# Power_Supply.net
KiCad netlist of a schematic drawn in Altium Designer
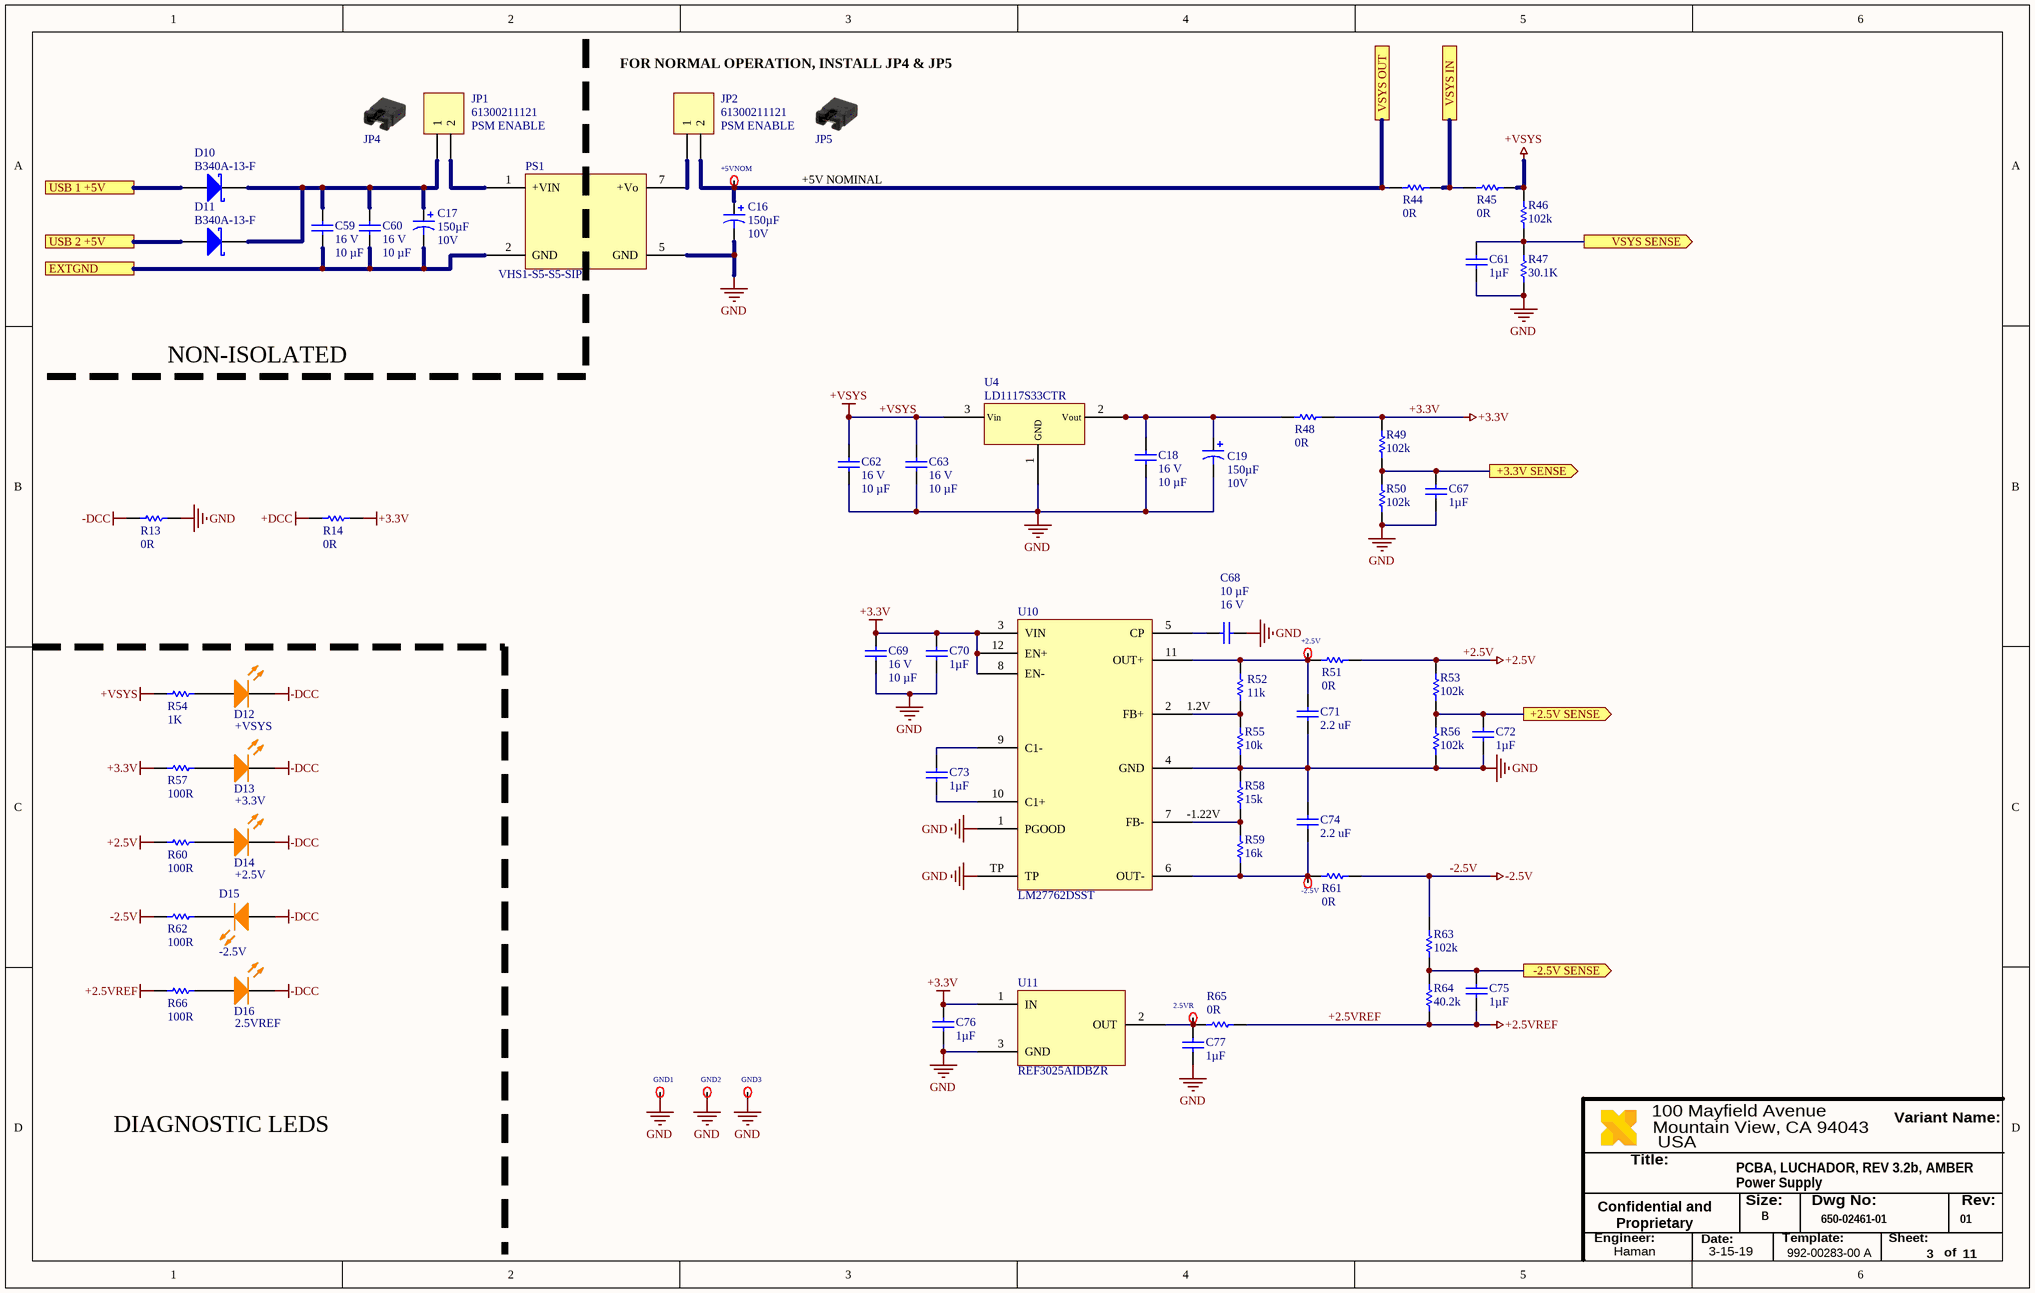
[diagram p0: Power Supply.SchDoc]

(export (version "E")
  (design (tool "Eeschema 10.0.6"))
  (components
    (comp (ref "+2.5V")
      (value "5001")
      (footprint "KEYSTONE TP")
      (fields (field (name "MANUFACTURER") "Keystone Electronics"))
      (libsource (lib "UTF SCHLIB") (part "5001"))
    )
    (comp (ref "+5VNOM")
      (value "5001")
      (footprint "KEYSTONE TP")
      (fields (field (name "MANUFACTURER") "Keystone Electronics"))
      (libsource (lib "UTF SCHLIB") (part "5001"))
    )
    (comp (ref "-2.5V")
      (value "5001")
      (footprint "KEYSTONE TP")
      (fields (field (name "MANUFACTURER") "Keystone Electronics"))
      (libsource (lib "UTF SCHLIB") (part "5001"))
    )
    (comp (ref "2.5VR")
      (value "5001")
      (footprint "KEYSTONE TP")
      (fields (field (name "MANUFACTURER") "Keystone Electronics"))
      (libsource (lib "UTF SCHLIB") (part "5001"))
    )
    (comp (ref "C16")
      (value "Cap Pol1")
      (footprint "2917")
      (description "Polarized Capacitor (Radial)")
      (fields
        (field (name "MANUFACTURER") "KEMET")
        (field (name "MANUFACTURER PART NUMBER") "T530D157M010ATE005")
        (field (name "CAPACITANCE") "150µF")
        (field (name "VOLTAGE - RATED") "10V")
      )
      (libsource (lib "Miscellaneous Devices") (part "Cap Pol1"))
    )
    (comp (ref "C17")
      (value "Cap Pol1")
      (footprint "2917")
      (description "Polarized Capacitor (Radial)")
      (fields
        (field (name "MANUFACTURER") "KEMET")
        (field (name "MANUFACTURER PART NUMBER") "T530D157M010ATE005")
        (field (name "CAPACITANCE") "150µF")
        (field (name "VOLTAGE - RATED") "10V")
      )
      (libsource (lib "Miscellaneous Devices") (part "Cap Pol1"))
    )
    (comp (ref "C18")
      (value "50V")
      (footprint "1206C")
      (description "CAP .1UF 50V CERAMIC Y5V 0805")
      (fields
        (field (name "MANUFACTURER") "Murata")
        (field (name "MANUFACTURER PART NUMBER") "GRM31CR71C106KA12L")
        (field (name "NOMINAL VOLTAGE") "16 V")
        (field (name "CAPACITY (ELEC.)") "10 µF")
      )
      (libsource (lib "Miscellaneous Devices") (part "Cap"))
    )
    (comp (ref "C19")
      (value "Cap Pol1")
      (footprint "2917")
      (description "Polarized Capacitor (Radial)")
      (fields
        (field (name "MANUFACTURER") "KEMET")
        (field (name "MANUFACTURER PART NUMBER") "T530D157M010ATE005")
        (field (name "CAPACITANCE") "150µF")
        (field (name "VOLTAGE - RATED") "10V")
      )
      (libsource (lib "Miscellaneous Devices") (part "Cap Pol1"))
    )
    (comp (ref "C59")
      (value "50V")
      (footprint "1206C")
      (description "CAP .1UF 50V CERAMIC Y5V 0805")
      (fields
        (field (name "MANUFACTURER") "Murata")
        (field (name "MANUFACTURER PART NUMBER") "GRM31CR71C106KA12L")
        (field (name "NOMINAL VOLTAGE") "16 V")
        (field (name "CAPACITY (ELEC.)") "10 µF")
      )
      (libsource (lib "Miscellaneous Devices") (part "Cap"))
    )
    (comp (ref "C60")
      (value "50V")
      (footprint "1206C")
      (description "CAP .1UF 50V CERAMIC Y5V 0805")
      (fields
        (field (name "MANUFACTURER") "Murata")
        (field (name "MANUFACTURER PART NUMBER") "GRM31CR71C106KA12L")
        (field (name "NOMINAL VOLTAGE") "16 V")
        (field (name "CAPACITY (ELEC.)") "10 µF")
      )
      (libsource (lib "Miscellaneous Devices") (part "Cap"))
    )
    (comp (ref "C61")
      (value "50V")
      (footprint "0402C")
      (description "CAP .1UF 50V CERAMIC Y5V 0805")
      (fields
        (field (name "MANUFACTURER") "TDK")
        (field (name "MANUFACTURER PART NUMBER") "CGB2A1JB1C105K033BC")
        (field (name "CAPACITANCE") "1µF")
      )
      (libsource (lib "Miscellaneous Devices") (part "Cap"))
    )
    (comp (ref "C62")
      (value "50V")
      (footprint "1206C")
      (description "CAP .1UF 50V CERAMIC Y5V 0805")
      (fields
        (field (name "MANUFACTURER") "Murata")
        (field (name "MANUFACTURER PART NUMBER") "GRM31CR71C106KA12L")
        (field (name "NOMINAL VOLTAGE") "16 V")
        (field (name "CAPACITY (ELEC.)") "10 µF")
      )
      (libsource (lib "Miscellaneous Devices") (part "Cap"))
    )
    (comp (ref "C63")
      (value "50V")
      (footprint "1206C")
      (description "CAP .1UF 50V CERAMIC Y5V 0805")
      (fields
        (field (name "MANUFACTURER") "Murata")
        (field (name "MANUFACTURER PART NUMBER") "GRM31CR71C106KA12L")
        (field (name "NOMINAL VOLTAGE") "16 V")
        (field (name "CAPACITY (ELEC.)") "10 µF")
      )
      (libsource (lib "Miscellaneous Devices") (part "Cap"))
    )
    (comp (ref "C67")
      (value "50V")
      (footprint "0402C")
      (description "CAP .1UF 50V CERAMIC Y5V 0805")
      (fields
        (field (name "MANUFACTURER") "TDK")
        (field (name "MANUFACTURER PART NUMBER") "CGB2A1JB1C105K033BC")
        (field (name "CAPACITANCE") "1µF")
      )
      (libsource (lib "Miscellaneous Devices") (part "Cap"))
    )
    (comp (ref "C68")
      (value "50V")
      (footprint "1206C")
      (description "CAP .1UF 50V CERAMIC Y5V 0805")
      (fields
        (field (name "MANUFACTURER") "Murata")
        (field (name "MANUFACTURER PART NUMBER") "GRM31CR71C106KA12L")
        (field (name "NOMINAL VOLTAGE") "16 V")
        (field (name "CAPACITY (ELEC.)") "10 µF")
      )
      (libsource (lib "Miscellaneous Devices") (part "Cap"))
    )
    (comp (ref "C69")
      (value "50V")
      (footprint "1206C")
      (description "CAP .1UF 50V CERAMIC Y5V 0805")
      (fields
        (field (name "MANUFACTURER") "Murata")
        (field (name "MANUFACTURER PART NUMBER") "GRM31CR71C106KA12L")
        (field (name "NOMINAL VOLTAGE") "16 V")
        (field (name "CAPACITY (ELEC.)") "10 µF")
      )
      (libsource (lib "Miscellaneous Devices") (part "Cap"))
    )
    (comp (ref "C70")
      (value "50V")
      (footprint "0402C")
      (description "CAP .1UF 50V CERAMIC Y5V 0805")
      (fields
        (field (name "MANUFACTURER") "TDK")
        (field (name "MANUFACTURER PART NUMBER") "CGB2A1JB1C105K033BC")
        (field (name "CAPACITANCE") "1µF")
      )
      (libsource (lib "Miscellaneous Devices") (part "Cap"))
    )
    (comp (ref "C71")
      (value "50V")
      (footprint "0402C")
      (description "CAP .1UF 50V CERAMIC Y5V 0805")
      (fields
        (field (name "MANUFACTURER") "Samsung")
        (field (name "MANUFACTURER PART NUMBER") "CL05A225KO5NQNC")
        (field (name "CAPACITANCE VALUE") "2.2 uF")
      )
      (libsource (lib "Miscellaneous Devices") (part "Cap"))
    )
    (comp (ref "C72")
      (value "50V")
      (footprint "0402C")
      (description "CAP .1UF 50V CERAMIC Y5V 0805")
      (fields
        (field (name "MANUFACTURER") "TDK")
        (field (name "MANUFACTURER PART NUMBER") "CGB2A1JB1C105K033BC")
        (field (name "CAPACITANCE") "1µF")
      )
      (libsource (lib "Miscellaneous Devices") (part "Cap"))
    )
    (comp (ref "C73")
      (value "50V")
      (footprint "0402C")
      (description "CAP .1UF 50V CERAMIC Y5V 0805")
      (fields
        (field (name "MANUFACTURER") "TDK")
        (field (name "MANUFACTURER PART NUMBER") "CGB2A1JB1C105K033BC")
        (field (name "CAPACITANCE") "1µF")
      )
      (libsource (lib "Miscellaneous Devices") (part "Cap"))
    )
    (comp (ref "C74")
      (value "50V")
      (footprint "0402C")
      (description "CAP .1UF 50V CERAMIC Y5V 0805")
      (fields
        (field (name "MANUFACTURER") "Samsung")
        (field (name "MANUFACTURER PART NUMBER") "CL05A225KO5NQNC")
        (field (name "CAPACITANCE VALUE") "2.2 uF")
      )
      (libsource (lib "Miscellaneous Devices") (part "Cap"))
    )
    (comp (ref "C75")
      (value "50V")
      (footprint "0402C")
      (description "CAP .1UF 50V CERAMIC Y5V 0805")
      (fields
        (field (name "MANUFACTURER") "TDK")
        (field (name "MANUFACTURER PART NUMBER") "CGB2A1JB1C105K033BC")
        (field (name "CAPACITANCE") "1µF")
      )
      (libsource (lib "Miscellaneous Devices") (part "Cap"))
    )
    (comp (ref "C76")
      (value "50V")
      (footprint "0402C")
      (description "CAP .1UF 50V CERAMIC Y5V 0805")
      (fields
        (field (name "MANUFACTURER") "TDK")
        (field (name "MANUFACTURER PART NUMBER") "CGB2A1JB1C105K033BC")
        (field (name "CAPACITANCE") "1µF")
      )
      (libsource (lib "Miscellaneous Devices") (part "Cap"))
    )
    (comp (ref "C77")
      (value "50V")
      (footprint "0402C")
      (description "CAP .1UF 50V CERAMIC Y5V 0805")
      (fields
        (field (name "MANUFACTURER") "TDK")
        (field (name "MANUFACTURER PART NUMBER") "CGB2A1JB1C105K033BC")
        (field (name "CAPACITANCE") "1µF")
      )
      (libsource (lib "Miscellaneous Devices") (part "Cap"))
    )
    (comp (ref "D10")
      (value "BAT46ZFILM")
      (footprint "SMA")
      (description "Schottky Rectifier")
      (fields
        (field (name "MANUFACTURER") "Diodes Incorporated")
        (field (name "MANUFACTURER PART NUMBER") "B340A-13-F")
      )
      (libsource (lib "EEG_SCHLIB") (part "BAT46ZFILM"))
    )
    (comp (ref "D11")
      (value "BAT46ZFILM")
      (footprint "SMA")
      (description "Schottky Rectifier")
      (fields
        (field (name "MANUFACTURER") "Diodes Incorporated")
        (field (name "MANUFACTURER PART NUMBER") "B340A-13-F")
      )
      (libsource (lib "EEG_SCHLIB") (part "BAT46ZFILM"))
    )
    (comp (ref "D12")
      (value "+VSYS")
      (footprint "0402L-ORANGE")
      (description "Typical INFRARED GaAs LED")
      (fields
        (field (name "MANUFACTURER") "Vishay")
        (field (name "MANUFACTURER PART NUMBER") "VLMO1500-GS08")
      )
      (libsource (lib "LUCHADOR SCHLIB") (part "LED0_1"))
    )
    (comp (ref "D13")
      (value "+3.3V")
      (footprint "0402L-ORANGE")
      (description "Typical INFRARED GaAs LED")
      (fields
        (field (name "MANUFACTURER") "Vishay")
        (field (name "MANUFACTURER PART NUMBER") "VLMO1500-GS08")
      )
      (libsource (lib "LUCHADOR SCHLIB") (part "LED0_1"))
    )
    (comp (ref "D14")
      (value "+2.5V")
      (footprint "0402L-ORANGE")
      (description "Typical INFRARED GaAs LED")
      (fields
        (field (name "MANUFACTURER") "Vishay")
        (field (name "MANUFACTURER PART NUMBER") "VLMO1500-GS08")
      )
      (libsource (lib "LUCHADOR SCHLIB") (part "LED0_1"))
    )
    (comp (ref "D15")
      (value "-2.5V")
      (footprint "0402L-ORANGE")
      (description "Typical INFRARED GaAs LED")
      (fields
        (field (name "MANUFACTURER") "Vishay")
        (field (name "MANUFACTURER PART NUMBER") "VLMO1500-GS08")
      )
      (libsource (lib "LUCHADOR SCHLIB") (part "LED0_1"))
    )
    (comp (ref "D16")
      (value "2.5VREF")
      (footprint "0402L-ORANGE")
      (description "Typical INFRARED GaAs LED")
      (fields
        (field (name "MANUFACTURER") "Vishay")
        (field (name "MANUFACTURER PART NUMBER") "VLMO1500-GS08")
      )
      (libsource (lib "LUCHADOR SCHLIB") (part "LED0_1"))
    )
    (comp (ref "GND1")
      (value "5001")
      (footprint "KEYSTONE TP")
      (fields (field (name "MANUFACTURER") "Keystone Electronics"))
      (libsource (lib "UTF SCHLIB") (part "5001"))
    )
    (comp (ref "GND2")
      (value "5001")
      (footprint "KEYSTONE TP")
      (fields (field (name "MANUFACTURER") "Keystone Electronics"))
      (libsource (lib "UTF SCHLIB") (part "5001"))
    )
    (comp (ref "GND3")
      (value "5001")
      (footprint "KEYSTONE TP")
      (fields (field (name "MANUFACTURER") "Keystone Electronics"))
      (libsource (lib "UTF SCHLIB") (part "5001"))
    )
    (comp (ref "JP1")
      (value "PSM ENABLE")
      (footprint "61300211121")
      (description "Header, 2-Pin")
      (fields
        (field (name "MANUFACTURER") "Wurth Electronics")
        (field (name "MANUFACTURER PART NUMBER") "61300211121")
      )
      (libsource (lib "Miscellaneous Connectors") (part "Header 2"))
    )
    (comp (ref "JP2")
      (value "PSM ENABLE")
      (footprint "61300211121")
      (description "Header, 2-Pin")
      (fields
        (field (name "MANUFACTURER") "Wurth Electronics")
        (field (name "MANUFACTURER PART NUMBER") "61300211121")
      )
      (libsource (lib "Miscellaneous Connectors") (part "Header 2"))
    )
    (comp (ref "JP4")
      (value "QPC02SXGN-RC")
      (fields (field (name "MANUFACTURER") "Sullins"))
      (libsource (lib "LUCHADOR SCHLIB") (part "QPC02SXGN-RC"))
    )
    (comp (ref "JP5")
      (value "QPC02SXGN-RC")
      (fields (field (name "MANUFACTURER") "Sullins"))
      (libsource (lib "LUCHADOR SCHLIB") (part "QPC02SXGN-RC"))
    )
    (comp (ref "PS1")
      (value "VHS1-S5-S5-SIP")
      (footprint "ISOLATED MODULE")
      (fields (field (name "MANUFACTURER") "CUI") (field (name "MANUFACTURER PART NUMBER") "VHS1-S5-S5-SIP"))
      (libsource (lib "LUCHADOR SCHLIB") (part "VHS1-S5-S5-SIP"))
    )
    (comp (ref "R13")
      (value "Res 0805")
      (footprint "0402R")
      (description "Resistor")
      (fields
        (field (name "MANUFACTURER") "Panasonic")
        (field (name "MANUFACTURER PART NUMBER") "ERJ-2GE0R00X")
        (field (name "RESISTANCE (OHMS)") "0R")
      )
      (libsource (lib "RAPTOR MCB SCHLIB") (part "Res 0805"))
    )
    (comp (ref "R14")
      (value "Res 0805")
      (footprint "0402R")
      (description "Resistor")
      (fields
        (field (name "MANUFACTURER") "Panasonic")
        (field (name "MANUFACTURER PART NUMBER") "ERJ-2GE0R00X")
        (field (name "RESISTANCE (OHMS)") "0R")
      )
      (libsource (lib "RAPTOR MCB SCHLIB") (part "Res 0805"))
    )
    (comp (ref "R44")
      (value "Res 0805")
      (footprint "0402R")
      (description "Resistor")
      (fields
        (field (name "MANUFACTURER") "Panasonic")
        (field (name "MANUFACTURER PART NUMBER") "ERJ-2GE0R00X")
        (field (name "RESISTANCE (OHMS)") "0R")
      )
      (libsource (lib "RAPTOR MCB SCHLIB") (part "Res 0805"))
    )
    (comp (ref "R45")
      (value "Res 0805")
      (footprint "0402R")
      (description "Resistor")
      (fields
        (field (name "MANUFACTURER") "Panasonic")
        (field (name "MANUFACTURER PART NUMBER") "ERJ-2GE0R00X")
        (field (name "RESISTANCE (OHMS)") "0R")
      )
      (libsource (lib "RAPTOR MCB SCHLIB") (part "Res 0805"))
    )
    (comp (ref "R46")
      (value "Res 0805")
      (footprint "0402R")
      (description "Resistor")
      (fields
        (field (name "MANUFACTURER") "Panasonic")
        (field (name "MANUFACTURER PART NUMBER") "ERJ-2RKF1023X")
        (field (name "RESISTANCE") "102k")
      )
      (libsource (lib "RAPTOR MCB SCHLIB") (part "Res 0805"))
    )
    (comp (ref "R47")
      (value "Res 0805")
      (footprint "0402R")
      (description "Resistor")
      (fields
        (field (name "MANUFACTURER") "Panasonic")
        (field (name "MANUFACTURER PART NUMBER") "ERJ-2RKF3012X")
        (field (name "RESISTANCE") "30.1K")
      )
      (libsource (lib "RAPTOR MCB SCHLIB") (part "Res 0805"))
    )
    (comp (ref "R48")
      (value "Res 0805")
      (footprint "0402R")
      (description "Resistor")
      (fields
        (field (name "MANUFACTURER") "Panasonic")
        (field (name "MANUFACTURER PART NUMBER") "ERJ-2GE0R00X")
        (field (name "RESISTANCE (OHMS)") "0R")
      )
      (libsource (lib "RAPTOR MCB SCHLIB") (part "Res 0805"))
    )
    (comp (ref "R49")
      (value "Res 0805")
      (footprint "0402R")
      (description "Resistor")
      (fields
        (field (name "MANUFACTURER") "Panasonic")
        (field (name "MANUFACTURER PART NUMBER") "ERJ-2RKF1023X")
        (field (name "RESISTANCE") "102k")
      )
      (libsource (lib "RAPTOR MCB SCHLIB") (part "Res 0805"))
    )
    (comp (ref "R50")
      (value "Res 0805")
      (footprint "0402R")
      (description "Resistor")
      (fields
        (field (name "MANUFACTURER") "Panasonic")
        (field (name "MANUFACTURER PART NUMBER") "ERJ-2RKF1023X")
        (field (name "RESISTANCE") "102k")
      )
      (libsource (lib "RAPTOR MCB SCHLIB") (part "Res 0805"))
    )
    (comp (ref "R51")
      (value "Res 0805")
      (footprint "0402R")
      (description "Resistor")
      (fields
        (field (name "MANUFACTURER") "Panasonic")
        (field (name "MANUFACTURER PART NUMBER") "ERJ-2GE0R00X")
        (field (name "RESISTANCE (OHMS)") "0R")
      )
      (libsource (lib "RAPTOR MCB SCHLIB") (part "Res 0805"))
    )
    (comp (ref "R52")
      (value "Res 0805")
      (footprint "0402R")
      (description "Resistor")
      (fields
        (field (name "MANUFACTURER") "Yageo")
        (field (name "MANUFACTURER PART NUMBER") "RC0402FR-0711KL")
        (field (name "RESISTANCE") "11k")
      )
      (libsource (lib "RAPTOR MCB SCHLIB") (part "Res 0805"))
    )
    (comp (ref "R53")
      (value "Res 0805")
      (footprint "0402R")
      (description "Resistor")
      (fields
        (field (name "MANUFACTURER") "Panasonic")
        (field (name "MANUFACTURER PART NUMBER") "ERJ-2RKF1023X")
        (field (name "RESISTANCE") "102k")
      )
      (libsource (lib "RAPTOR MCB SCHLIB") (part "Res 0805"))
    )
    (comp (ref "R54")
      (value "Res 0805")
      (footprint "0402R")
      (description "Resistor")
      (fields
        (field (name "MANUFACTURER") "Yageo")
        (field (name "MANUFACTURER PART NUMBER") "RC0402FR-071KL")
        (field (name "RESISTANCE") "1K")
      )
      (libsource (lib "RAPTOR MCB SCHLIB") (part "Res 0805"))
    )
    (comp (ref "R55")
      (value "Res 0805")
      (footprint "0402R")
      (description "Resistor")
      (fields
        (field (name "MANUFACTURER") "Samsung")
        (field (name "MANUFACTURER PART NUMBER") "RC1005F103CS")
        (field (name "RESISTANCE") "10k")
      )
      (libsource (lib "RAPTOR MCB SCHLIB") (part "Res 0805"))
    )
    (comp (ref "R56")
      (value "Res 0805")
      (footprint "0402R")
      (description "Resistor")
      (fields
        (field (name "MANUFACTURER") "Panasonic")
        (field (name "MANUFACTURER PART NUMBER") "ERJ-2RKF1023X")
        (field (name "RESISTANCE") "102k")
      )
      (libsource (lib "RAPTOR MCB SCHLIB") (part "Res 0805"))
    )
    (comp (ref "R57")
      (value "Res 0805")
      (footprint "0402R")
      (description "Resistor")
      (fields
        (field (name "MANUFACTURER") "Panasonic")
        (field (name "MANUFACTURER PART NUMBER") "ERJ-2RKF1000X")
        (field (name "RESISTANCE") "100R")
      )
      (libsource (lib "RAPTOR MCB SCHLIB") (part "Res 0805"))
    )
    (comp (ref "R58")
      (value "Res 0805")
      (footprint "0402R")
      (description "Resistor")
      (fields
        (field (name "MANUFACTURER") "Panasonic")
        (field (name "MANUFACTURER PART NUMBER") "ERJ-2RKF1502X")
        (field (name "RESISTANCE") "15k")
      )
      (libsource (lib "RAPTOR MCB SCHLIB") (part "Res 0805"))
    )
    (comp (ref "R59")
      (value "Res 0805")
      (footprint "0402R")
      (description "Resistor")
      (fields
        (field (name "MANUFACTURER") "Panasonic")
        (field (name "MANUFACTURER PART NUMBER") "ERJ-2RKF1602X")
        (field (name "RESISTANCE") "16k")
      )
      (libsource (lib "RAPTOR MCB SCHLIB") (part "Res 0805"))
    )
    (comp (ref "R60")
      (value "Res 0805")
      (footprint "0402R")
      (description "Resistor")
      (fields
        (field (name "MANUFACTURER") "Panasonic")
        (field (name "MANUFACTURER PART NUMBER") "ERJ-2RKF1000X")
        (field (name "RESISTANCE") "100R")
      )
      (libsource (lib "RAPTOR MCB SCHLIB") (part "Res 0805"))
    )
    (comp (ref "R61")
      (value "Res 0805")
      (footprint "0402R")
      (description "Resistor")
      (fields
        (field (name "MANUFACTURER") "Panasonic")
        (field (name "MANUFACTURER PART NUMBER") "ERJ-2GE0R00X")
        (field (name "RESISTANCE (OHMS)") "0R")
      )
      (libsource (lib "RAPTOR MCB SCHLIB") (part "Res 0805"))
    )
    (comp (ref "R62")
      (value "Res 0805")
      (footprint "0402R")
      (description "Resistor")
      (fields
        (field (name "MANUFACTURER") "Panasonic")
        (field (name "MANUFACTURER PART NUMBER") "ERJ-2RKF1000X")
        (field (name "RESISTANCE") "100R")
      )
      (libsource (lib "RAPTOR MCB SCHLIB") (part "Res 0805"))
    )
    (comp (ref "R63")
      (value "Res 0805")
      (footprint "0402R")
      (description "Resistor")
      (fields
        (field (name "MANUFACTURER") "Panasonic")
        (field (name "MANUFACTURER PART NUMBER") "ERJ-2RKF1023X")
        (field (name "RESISTANCE") "102k")
      )
      (libsource (lib "RAPTOR MCB SCHLIB") (part "Res 0805"))
    )
    (comp (ref "R64")
      (value "Res 0805")
      (footprint "0402R")
      (description "Resistor")
      (fields
        (field (name "MANUFACTURER") "Panasonic")
        (field (name "MANUFACTURER PART NUMBER") "ERJ-2RKF4022X")
        (field (name "RESISTANCE") "40.2k")
      )
      (libsource (lib "RAPTOR MCB SCHLIB") (part "Res 0805"))
    )
    (comp (ref "R65")
      (value "Res 0805")
      (footprint "0402R")
      (description "Resistor")
      (fields
        (field (name "MANUFACTURER") "Panasonic")
        (field (name "MANUFACTURER PART NUMBER") "ERJ-2GE0R00X")
        (field (name "RESISTANCE (OHMS)") "0R")
      )
      (libsource (lib "RAPTOR MCB SCHLIB") (part "Res 0805"))
    )
    (comp (ref "R66")
      (value "Res 0805")
      (footprint "0402R")
      (description "Resistor")
      (fields
        (field (name "MANUFACTURER") "Panasonic")
        (field (name "MANUFACTURER PART NUMBER") "ERJ-2RKF1000X")
        (field (name "RESISTANCE") "100R")
      )
      (libsource (lib "RAPTOR MCB SCHLIB") (part "Res 0805"))
    )
    (comp (ref "U4")
      (value "LD1117S33CTR")
      (footprint "SOT-223")
      (fields
        (field (name "MANUFACTURER") "STMicroelectronics")
        (field (name "MANUFACTURER PART NUMBER") "LD1117S33CTR")
      )
      (libsource (lib "EEG_SCHLIB") (part "LD1117S33CTR"))
    )
    (comp (ref "U10")
      (value "LM27762DSST")
      (footprint "WFDFN-12")
      (fields
        (field (name "MANUFACTURER") "Texas Instruments")
        (field (name "MANUFACTURER PART NUMBER") "LM27762DSST")
      )
      (libsource (lib "LUCHADOR SCHLIB") (part "LM27762DSST"))
    )
    (comp (ref "U11")
      (value "REF3025AIDBZR")
      (footprint "SOT-23")
      (fields
        (field (name "MANUFACTURER") "Texas Instruments")
        (field (name "TOLERANCE") "±0.2%")
        (field (name "MANUFACTURER PART NUMBER") "REF3025AIDBZR")
      )
      (libsource (lib "LUCHADOR SCHLIB") (part "REF3025AIDBZR"))
    )
  )
  (nets
    (net (code "1") (name "+2.5V") (class "Default")
      (node (ref "R51") (pin "2") (pinfunction "2_2") (pintype "passive"))
      (node (ref "R53") (pin "2") (pinfunction "2_2") (pintype "passive"))
      (node (ref "R60") (pin "1") (pinfunction "1_1") (pintype "passive"))
    )
    (net (code "2") (name "+2.5VREF") (class "Default")
      (node (ref "C75") (pin "2") (pinfunction "2_2") (pintype "passive"))
      (node (ref "R64") (pin "1") (pinfunction "1_1") (pintype "passive"))
      (node (ref "R65") (pin "2") (pinfunction "2_2") (pintype "passive"))
      (node (ref "R66") (pin "1") (pinfunction "1_1") (pintype "passive"))
    )
    (net (code "3") (name "+3.3V") (class "Default")
      (node (ref "C69") (pin "1") (pinfunction "1_1") (pintype "passive"))
      (node (ref "C70") (pin "1") (pinfunction "1_1") (pintype "passive"))
      (node (ref "C76") (pin "1") (pinfunction "1_1") (pintype "passive"))
      (node (ref "R14") (pin "2") (pinfunction "2_2") (pintype "passive"))
      (node (ref "R48") (pin "2") (pinfunction "2_2") (pintype "passive"))
      (node (ref "R49") (pin "2") (pinfunction "2_2") (pintype "passive"))
      (node (ref "R57") (pin "1") (pinfunction "1_1") (pintype "passive"))
      (node (ref "U10") (pin "12") (pinfunction "EN+_12") (pintype "passive"))
      (node (ref "U10") (pin "3") (pinfunction "VIN_3") (pintype "passive"))
      (node (ref "U10") (pin "8") (pinfunction "EN-_8") (pintype "passive"))
      (node (ref "U11") (pin "1") (pinfunction "IN_1") (pintype "passive"))
    )
    (net (code "4") (name "+DCC") (class "Default")
      (node (ref "R14") (pin "1") (pinfunction "1_1") (pintype "passive"))
    )
    (net (code "5") (name "+VSYS") (class "Default")
      (node (ref "C62") (pin "1") (pinfunction "1_1") (pintype "passive"))
      (node (ref "C63") (pin "1") (pinfunction "1_1") (pintype "passive"))
      (node (ref "R45") (pin "2") (pinfunction "2_2") (pintype "passive"))
      (node (ref "R46") (pin "2") (pinfunction "2_2") (pintype "passive"))
      (node (ref "R54") (pin "1") (pinfunction "1_1") (pintype "passive"))
      (node (ref "U4") (pin "3") (pinfunction "Vin_3") (pintype "power_in"))
    )
    (net (code "6") (name "-2.5V") (class "Default")
      (node (ref "R61") (pin "2") (pinfunction "2_2") (pintype "passive"))
      (node (ref "R62") (pin "1") (pinfunction "1_1") (pintype "passive"))
      (node (ref "R63") (pin "2") (pinfunction "2_2") (pintype "passive"))
    )
    (net (code "7") (name "-DCC") (class "Default")
      (node (ref "D12") (pin "2") (pinfunction "K_2") (pintype "passive"))
      (node (ref "D13") (pin "2") (pinfunction "K_2") (pintype "passive"))
      (node (ref "D14") (pin "2") (pinfunction "K_2") (pintype "passive"))
      (node (ref "D15") (pin "1") (pinfunction "A_1") (pintype "passive"))
      (node (ref "D16") (pin "2") (pinfunction "K_2") (pintype "passive"))
      (node (ref "R13") (pin "1") (pinfunction "1_1") (pintype "passive"))
    )
    (net (code "8") (name "/+2.5V SENSE") (class "Default")
      (node (ref "C72") (pin "1") (pinfunction "1_1") (pintype "passive"))
      (node (ref "R53") (pin "1") (pinfunction "1_1") (pintype "passive"))
      (node (ref "R56") (pin "2") (pinfunction "2_2") (pintype "passive"))
    )
    (net (code "9") (name "/+3.3V SENSE") (class "Default")
      (node (ref "C67") (pin "1") (pinfunction "1_1") (pintype "passive"))
      (node (ref "R49") (pin "1") (pinfunction "1_1") (pintype "passive"))
      (node (ref "R50") (pin "2") (pinfunction "2_2") (pintype "passive"))
    )
    (net (code "10") (name "/-2.5V SENSE") (class "Default")
      (node (ref "C75") (pin "1") (pinfunction "1_1") (pintype "passive"))
      (node (ref "R63") (pin "1") (pinfunction "1_1") (pintype "passive"))
      (node (ref "R64") (pin "2") (pinfunction "2_2") (pintype "passive"))
    )
    (net (code "11") (name "/EXTGND") (class "Default")
      (node (ref "C17") (pin "2") (pinfunction "2_2") (pintype "passive"))
      (node (ref "C59") (pin "2") (pinfunction "2_2") (pintype "passive"))
      (node (ref "C60") (pin "2") (pinfunction "2_2") (pintype "passive"))
      (node (ref "PS1") (pin "2") (pinfunction "GND_2") (pintype "passive"))
    )
    (net (code "12") (name "/USB 1 +5V") (class "Default")
      (node (ref "D10") (pin "1") (pinfunction "A_1") (pintype "passive"))
    )
    (net (code "13") (name "/USB 2 +5V") (class "Default")
      (node (ref "D11") (pin "1") (pinfunction "A_1") (pintype "passive"))
    )
    (net (code "14") (name "/VSYS IN") (class "Default")
      (node (ref "R44") (pin "2") (pinfunction "2_2") (pintype "passive"))
      (node (ref "R45") (pin "1") (pinfunction "1_1") (pintype "passive"))
    )
    (net (code "15") (name "/VSYS OUT") (class "Default")
      (node (ref "+5VNOM") (pin "1") (pinfunction "1_1") (pintype "passive"))
      (node (ref "C16") (pin "1") (pinfunction "1_1") (pintype "passive"))
      (node (ref "JP2") (pin "2") (pinfunction "2_2") (pintype "passive"))
      (node (ref "R44") (pin "1") (pinfunction "1_1") (pintype "passive"))
    )
    (net (code "16") (name "/VSYS SENSE") (class "Default")
      (node (ref "C61") (pin "1") (pinfunction "1_1") (pintype "passive"))
      (node (ref "R46") (pin "1") (pinfunction "1_1") (pintype "passive"))
      (node (ref "R47") (pin "2") (pinfunction "2_2") (pintype "passive"))
    )
    (net (code "17") (name "GND") (class "Default")
      (node (ref "C16") (pin "2") (pinfunction "2_2") (pintype "passive"))
      (node (ref "C18") (pin "2") (pinfunction "2_2") (pintype "passive"))
      (node (ref "C19") (pin "2") (pinfunction "2_2") (pintype "passive"))
      (node (ref "C61") (pin "2") (pinfunction "2_2") (pintype "passive"))
      (node (ref "C62") (pin "2") (pinfunction "2_2") (pintype "passive"))
      (node (ref "C63") (pin "2") (pinfunction "2_2") (pintype "passive"))
      (node (ref "C67") (pin "2") (pinfunction "2_2") (pintype "passive"))
      (node (ref "C68") (pin "2") (pinfunction "2_2") (pintype "passive"))
      (node (ref "C69") (pin "2") (pinfunction "2_2") (pintype "passive"))
      (node (ref "C70") (pin "2") (pinfunction "2_2") (pintype "passive"))
      (node (ref "C71") (pin "2") (pinfunction "2_2") (pintype "passive"))
      (node (ref "C72") (pin "2") (pinfunction "2_2") (pintype "passive"))
      (node (ref "C74") (pin "1") (pinfunction "1_1") (pintype "passive"))
      (node (ref "C76") (pin "2") (pinfunction "2_2") (pintype "passive"))
      (node (ref "C77") (pin "2") (pinfunction "2_2") (pintype "passive"))
      (node (ref "GND1") (pin "1") (pinfunction "1_1") (pintype "passive"))
      (node (ref "GND2") (pin "1") (pinfunction "1_1") (pintype "passive"))
      (node (ref "GND3") (pin "1") (pinfunction "1_1") (pintype "passive"))
      (node (ref "PS1") (pin "5") (pinfunction "GND_5") (pintype "passive"))
      (node (ref "R13") (pin "2") (pinfunction "2_2") (pintype "passive"))
      (node (ref "R47") (pin "1") (pinfunction "1_1") (pintype "passive"))
      (node (ref "R50") (pin "1") (pinfunction "1_1") (pintype "passive"))
      (node (ref "R55") (pin "1") (pinfunction "1_1") (pintype "passive"))
      (node (ref "R56") (pin "1") (pinfunction "1_1") (pintype "passive"))
      (node (ref "R58") (pin "2") (pinfunction "2_2") (pintype "passive"))
      (node (ref "U10") (pin "1") (pinfunction "PGOOD_1") (pintype "passive"))
      (node (ref "U10") (pin "4") (pinfunction "GND_4") (pintype "passive"))
      (node (ref "U10") (pin "TP") (pinfunction "TP_TP") (pintype "passive"))
      (node (ref "U11") (pin "3") (pinfunction "GND_3") (pintype "passive"))
      (node (ref "U4") (pin "1") (pinfunction "GND_1") (pintype "power_in"))
    )
    (net (code "18") (name "Net-(C18-Pad1)") (class "Default")
      (node (ref "C18") (pin "1") (pinfunction "1_1") (pintype "passive"))
      (node (ref "C19") (pin "1") (pinfunction "1_1") (pintype "passive"))
      (node (ref "R48") (pin "1") (pinfunction "1_1") (pintype "passive"))
      (node (ref "U4") (pin "2") (pinfunction "Vout_2") (pintype "power_in"))
      (node (ref "U4") (pin "4") (pinfunction "Vout_4") (pintype "power_in"))
    )
    (net (code "19") (name "Net-(D10-K)") (class "Default")
      (node (ref "C17") (pin "1") (pinfunction "1_1") (pintype "passive"))
      (node (ref "C59") (pin "1") (pinfunction "1_1") (pintype "passive"))
      (node (ref "C60") (pin "1") (pinfunction "1_1") (pintype "passive"))
      (node (ref "D10") (pin "2") (pinfunction "K_2") (pintype "passive"))
      (node (ref "D11") (pin "2") (pinfunction "K_2") (pintype "passive"))
      (node (ref "JP1") (pin "1") (pinfunction "1_1") (pintype "passive"))
    )
    (net (code "20") (name "Net-(D12-A)") (class "Default")
      (node (ref "D12") (pin "1") (pinfunction "A_1") (pintype "passive"))
      (node (ref "R54") (pin "2") (pinfunction "2_2") (pintype "passive"))
    )
    (net (code "21") (name "Net-(D13-A)") (class "Default")
      (node (ref "D13") (pin "1") (pinfunction "A_1") (pintype "passive"))
      (node (ref "R57") (pin "2") (pinfunction "2_2") (pintype "passive"))
    )
    (net (code "22") (name "Net-(D14-A)") (class "Default")
      (node (ref "D14") (pin "1") (pinfunction "A_1") (pintype "passive"))
      (node (ref "R60") (pin "2") (pinfunction "2_2") (pintype "passive"))
    )
    (net (code "23") (name "Net-(D15-K)") (class "Default")
      (node (ref "D15") (pin "2") (pinfunction "K_2") (pintype "passive"))
      (node (ref "R62") (pin "2") (pinfunction "2_2") (pintype "passive"))
    )
    (net (code "24") (name "Net-(D16-A)") (class "Default")
      (node (ref "D16") (pin "1") (pinfunction "A_1") (pintype "passive"))
      (node (ref "R66") (pin "2") (pinfunction "2_2") (pintype "passive"))
    )
    (net (code "25") (name "Net-(PS1-+VIN)") (class "Default")
      (node (ref "JP1") (pin "2") (pinfunction "2_2") (pintype "passive"))
      (node (ref "PS1") (pin "1") (pinfunction "+VIN_1") (pintype "passive"))
    )
    (net (code "26") (name "Net-(PS1-+Vo)") (class "Default")
      (node (ref "JP2") (pin "1") (pinfunction "1_1") (pintype "passive"))
      (node (ref "PS1") (pin "7") (pinfunction "+Vo_7") (pintype "passive"))
    )
    (net (code "27") (name "Net-(U10-C1+)") (class "Default")
      (node (ref "C73") (pin "2") (pinfunction "2_2") (pintype "passive"))
      (node (ref "U10") (pin "10") (pinfunction "C1+_10") (pintype "passive"))
    )
    (net (code "28") (name "Net-(U10-C1-)") (class "Default")
      (node (ref "C73") (pin "1") (pinfunction "1_1") (pintype "passive"))
      (node (ref "U10") (pin "9") (pinfunction "C1-_9") (pintype "passive"))
    )
    (net (code "29") (name "Net-(U10-CP)") (class "Default")
      (node (ref "C68") (pin "1") (pinfunction "1_1") (pintype "passive"))
      (node (ref "U10") (pin "5") (pinfunction "CP_5") (pintype "passive"))
    )
    (net (code "30") (name "Net-(U10-FB+)") (class "Default")
      (node (ref "R52") (pin "1") (pinfunction "1_1") (pintype "passive"))
      (node (ref "R55") (pin "2") (pinfunction "2_2") (pintype "passive"))
      (node (ref "U10") (pin "2") (pinfunction "FB+_2") (pintype "passive"))
    )
    (net (code "31") (name "Net-(U10-FB-)") (class "Default")
      (node (ref "R58") (pin "1") (pinfunction "1_1") (pintype "passive"))
      (node (ref "R59") (pin "2") (pinfunction "2_2") (pintype "passive"))
      (node (ref "U10") (pin "7") (pinfunction "FB-_7") (pintype "passive"))
    )
    (net (code "32") (name "Net-(U10-OUT+)") (class "Default")
      (node (ref "+2.5V") (pin "1") (pinfunction "1_1") (pintype "passive"))
      (node (ref "C71") (pin "1") (pinfunction "1_1") (pintype "passive"))
      (node (ref "R51") (pin "1") (pinfunction "1_1") (pintype "passive"))
      (node (ref "R52") (pin "2") (pinfunction "2_2") (pintype "passive"))
      (node (ref "U10") (pin "11") (pinfunction "OUT+_11") (pintype "passive"))
    )
    (net (code "33") (name "Net-(U10-OUT-)") (class "Default")
      (node (ref "-2.5V") (pin "1") (pinfunction "1_1") (pintype "passive"))
      (node (ref "C74") (pin "2") (pinfunction "2_2") (pintype "passive"))
      (node (ref "R59") (pin "1") (pinfunction "1_1") (pintype "passive"))
      (node (ref "R61") (pin "1") (pinfunction "1_1") (pintype "passive"))
      (node (ref "U10") (pin "6") (pinfunction "OUT-_6") (pintype "passive"))
    )
    (net (code "34") (name "Net-(U11-OUT)") (class "Default")
      (node (ref "2.5VR") (pin "1") (pinfunction "1_1") (pintype "passive"))
      (node (ref "C77") (pin "1") (pinfunction "1_1") (pintype "passive"))
      (node (ref "R65") (pin "1") (pinfunction "1_1") (pintype "passive"))
      (node (ref "U11") (pin "2") (pinfunction "OUT_2") (pintype "passive"))
    )
  )
)
